# 7seg.net
KiCad netlist of a schematic drawn in EAGLE
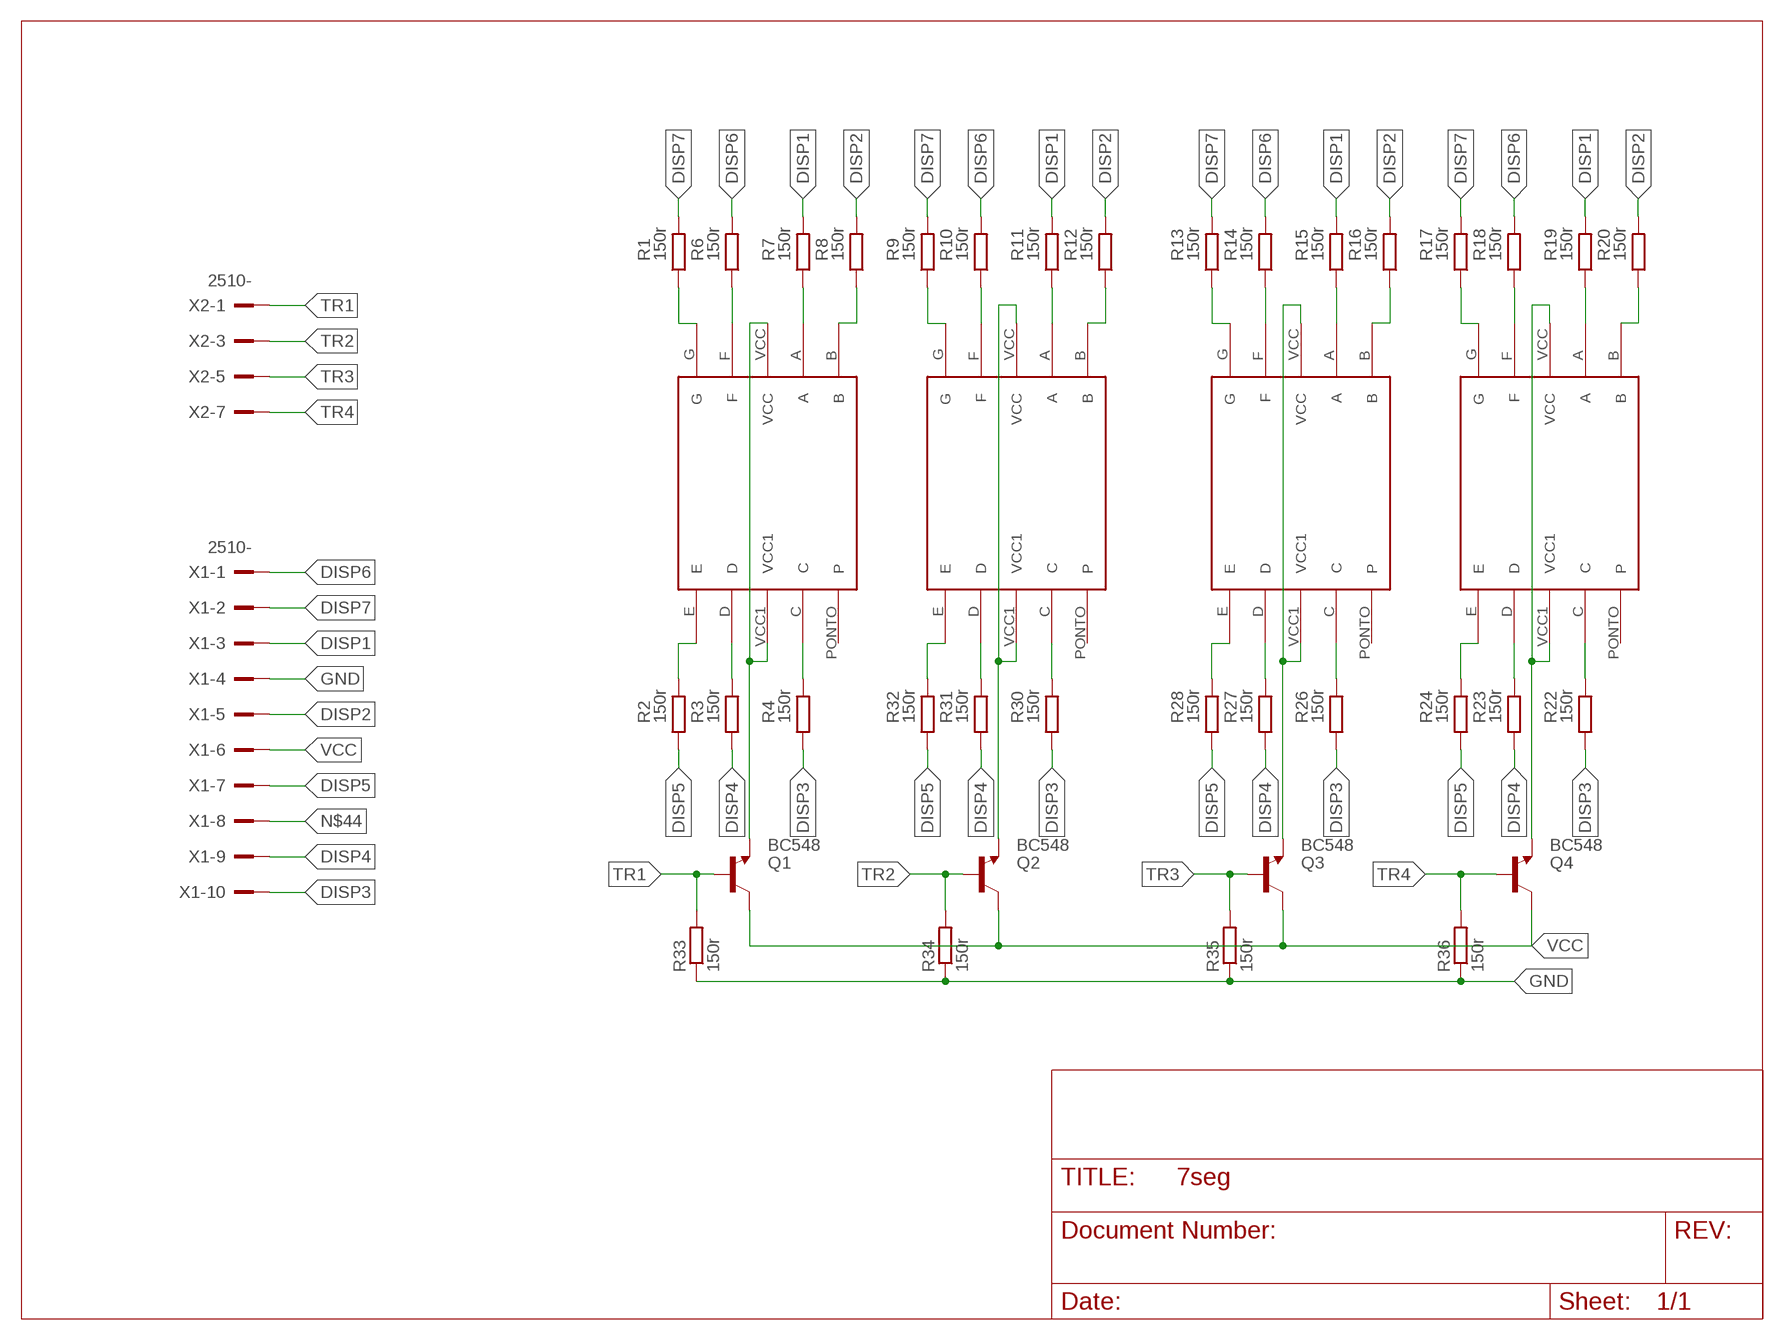
[diagram p0: schematic, sheet 1]

(export (version "E")
  (design (tool "Eeschema 10.0.6"))
  (components
    (comp (ref "Q1")
      (value "BC548")
      (footprint "eagle-import:TO92-EBC")
      (libsource (lib "eagle-import") (part "BC548"))
    )
    (comp (ref "Q2")
      (value "BC548")
      (footprint "eagle-import:TO92-EBC")
      (libsource (lib "eagle-import") (part "BC548"))
    )
    (comp (ref "Q3")
      (value "BC548")
      (footprint "eagle-import:TO92-EBC")
      (libsource (lib "eagle-import") (part "BC548"))
    )
    (comp (ref "Q4")
      (value "BC548")
      (footprint "eagle-import:TO92-EBC")
      (libsource (lib "eagle-import") (part "BC548"))
    )
    (comp (ref "R1")
      (value "150r")
      (footprint "eagle-import:0204_ELVYS")
      (libsource (lib "eagle-import") (part "R-EU_"))
    )
    (comp (ref "R2")
      (value "150r")
      (footprint "eagle-import:0204_ELVYS")
      (libsource (lib "eagle-import") (part "R-EU_"))
    )
    (comp (ref "R3")
      (value "150r")
      (footprint "eagle-import:0204_ELVYS")
      (libsource (lib "eagle-import") (part "R-EU_"))
    )
    (comp (ref "R4")
      (value "150r")
      (footprint "eagle-import:0204_ELVYS")
      (libsource (lib "eagle-import") (part "R-EU_"))
    )
    (comp (ref "R6")
      (value "150r")
      (footprint "eagle-import:0204_ELVYS")
      (libsource (lib "eagle-import") (part "R-EU_"))
    )
    (comp (ref "R7")
      (value "150r")
      (footprint "eagle-import:0204_ELVYS")
      (libsource (lib "eagle-import") (part "R-EU_"))
    )
    (comp (ref "R8")
      (value "150r")
      (footprint "eagle-import:0204_ELVYS")
      (libsource (lib "eagle-import") (part "R-EU_"))
    )
    (comp (ref "R9")
      (value "150r")
      (footprint "eagle-import:0204_ELVYS")
      (libsource (lib "eagle-import") (part "R-EU_"))
    )
    (comp (ref "R10")
      (value "150r")
      (footprint "eagle-import:0204_ELVYS")
      (libsource (lib "eagle-import") (part "R-EU_"))
    )
    (comp (ref "R11")
      (value "150r")
      (footprint "eagle-import:0204_ELVYS")
      (libsource (lib "eagle-import") (part "R-EU_"))
    )
    (comp (ref "R12")
      (value "150r")
      (footprint "eagle-import:0204_ELVYS")
      (libsource (lib "eagle-import") (part "R-EU_"))
    )
    (comp (ref "R13")
      (value "150r")
      (footprint "eagle-import:0204_ELVYS")
      (libsource (lib "eagle-import") (part "R-EU_"))
    )
    (comp (ref "R14")
      (value "150r")
      (footprint "eagle-import:0204_ELVYS")
      (libsource (lib "eagle-import") (part "R-EU_"))
    )
    (comp (ref "R15")
      (value "150r")
      (footprint "eagle-import:0204_ELVYS")
      (libsource (lib "eagle-import") (part "R-EU_"))
    )
    (comp (ref "R16")
      (value "150r")
      (footprint "eagle-import:0204_ELVYS")
      (libsource (lib "eagle-import") (part "R-EU_"))
    )
    (comp (ref "R17")
      (value "150r")
      (footprint "eagle-import:0204_ELVYS")
      (libsource (lib "eagle-import") (part "R-EU_"))
    )
    (comp (ref "R18")
      (value "150r")
      (footprint "eagle-import:0204_ELVYS")
      (libsource (lib "eagle-import") (part "R-EU_"))
    )
    (comp (ref "R19")
      (value "150r")
      (footprint "eagle-import:0204_ELVYS")
      (libsource (lib "eagle-import") (part "R-EU_"))
    )
    (comp (ref "R20")
      (value "150r")
      (footprint "eagle-import:0204_ELVYS")
      (libsource (lib "eagle-import") (part "R-EU_"))
    )
    (comp (ref "R22")
      (value "150r")
      (footprint "eagle-import:0204_ELVYS")
      (libsource (lib "eagle-import") (part "R-EU_"))
    )
    (comp (ref "R23")
      (value "150r")
      (footprint "eagle-import:0204_ELVYS")
      (libsource (lib "eagle-import") (part "R-EU_"))
    )
    (comp (ref "R24")
      (value "150r")
      (footprint "eagle-import:0204_ELVYS")
      (libsource (lib "eagle-import") (part "R-EU_"))
    )
    (comp (ref "R26")
      (value "150r")
      (footprint "eagle-import:0204_ELVYS")
      (libsource (lib "eagle-import") (part "R-EU_"))
    )
    (comp (ref "R27")
      (value "150r")
      (footprint "eagle-import:0204_ELVYS")
      (libsource (lib "eagle-import") (part "R-EU_"))
    )
    (comp (ref "R28")
      (value "150r")
      (footprint "eagle-import:0204_ELVYS")
      (libsource (lib "eagle-import") (part "R-EU_"))
    )
    (comp (ref "R30")
      (value "150r")
      (footprint "eagle-import:0204_ELVYS")
      (libsource (lib "eagle-import") (part "R-EU_"))
    )
    (comp (ref "R31")
      (value "150r")
      (footprint "eagle-import:0204_ELVYS")
      (libsource (lib "eagle-import") (part "R-EU_"))
    )
    (comp (ref "R32")
      (value "150r")
      (footprint "eagle-import:0204_ELVYS")
      (libsource (lib "eagle-import") (part "R-EU_"))
    )
    (comp (ref "R33")
      (value "150r")
      (footprint "eagle-import:0204_ELVYS")
      (libsource (lib "eagle-import") (part "R-EU_"))
    )
    (comp (ref "R34")
      (value "150r")
      (footprint "eagle-import:0204_ELVYS")
      (libsource (lib "eagle-import") (part "R-EU_"))
    )
    (comp (ref "R35")
      (value "150r")
      (footprint "eagle-import:0204_ELVYS")
      (libsource (lib "eagle-import") (part "R-EU_"))
    )
    (comp (ref "R36")
      (value "150r")
      (footprint "eagle-import:0204_ELVYS")
      (libsource (lib "eagle-import") (part "R-EU_"))
    )
    (comp (ref "U$1")
      (value "HS-12101BS")
      (footprint "eagle-import:HS-12101BS")
      (libsource (lib "eagle-import") (part "HS-12101BS"))
    )
    (comp (ref "U$2")
      (value "HS-12101BS")
      (footprint "eagle-import:HS-12101BS")
      (libsource (lib "eagle-import") (part "HS-12101BS"))
    )
    (comp (ref "U$3")
      (value "HS-12101BS")
      (footprint "eagle-import:HS-12101BS")
      (libsource (lib "eagle-import") (part "HS-12101BS"))
    )
    (comp (ref "U$4")
      (value "HS-12101BS")
      (footprint "eagle-import:HS-12101BS")
      (libsource (lib "eagle-import") (part "HS-12101BS"))
    )
    (comp (ref "X1")
      (value "2510-")
      (footprint "eagle-import:PAK100_2500-10")
      (fields (field (name "MF") "3M") (field (name "MPN") "2510-6002UB"))
      (libsource (lib "eagle-import") (part "2510-"))
    )
    (comp (ref "X2")
      (value "2510-")
      (footprint "eagle-import:PAK100_2500-10")
      (fields (field (name "MF") "3M") (field (name "MPN") "2510-6002UB"))
      (libsource (lib "eagle-import") (part "2510-"))
    )
  )
  (nets
    (net (code "1") (name "DISP1") (class "Default")
      (node (ref "R11") (pin "P$2") (pinfunction "2_P$2") (pintype "passive"))
      (node (ref "R15") (pin "P$2") (pinfunction "2_P$2") (pintype "passive"))
      (node (ref "R19") (pin "P$2") (pinfunction "2_P$2") (pintype "passive"))
      (node (ref "R7") (pin "P$2") (pinfunction "2_P$2") (pintype "passive"))
      (node (ref "X1") (pin "3") (pinfunction "KL_3") (pintype "passive"))
    )
    (net (code "2") (name "DISP2") (class "Default")
      (node (ref "R12") (pin "P$2") (pinfunction "2_P$2") (pintype "passive"))
      (node (ref "R16") (pin "P$2") (pinfunction "2_P$2") (pintype "passive"))
      (node (ref "R20") (pin "P$2") (pinfunction "2_P$2") (pintype "passive"))
      (node (ref "R8") (pin "P$2") (pinfunction "2_P$2") (pintype "passive"))
      (node (ref "X1") (pin "5") (pinfunction "KL_5") (pintype "passive"))
    )
    (net (code "3") (name "DISP3") (class "Default")
      (node (ref "R22") (pin "P$1") (pinfunction "1_P$1") (pintype "passive"))
      (node (ref "R26") (pin "P$1") (pinfunction "1_P$1") (pintype "passive"))
      (node (ref "R30") (pin "P$1") (pinfunction "1_P$1") (pintype "passive"))
      (node (ref "R4") (pin "P$1") (pinfunction "1_P$1") (pintype "passive"))
      (node (ref "X1") (pin "10") (pinfunction "KL_10") (pintype "passive"))
    )
    (net (code "4") (name "DISP4") (class "Default")
      (node (ref "R23") (pin "P$1") (pinfunction "1_P$1") (pintype "passive"))
      (node (ref "R27") (pin "P$1") (pinfunction "1_P$1") (pintype "passive"))
      (node (ref "R3") (pin "P$1") (pinfunction "1_P$1") (pintype "passive"))
      (node (ref "R31") (pin "P$1") (pinfunction "1_P$1") (pintype "passive"))
      (node (ref "X1") (pin "9") (pinfunction "KL_9") (pintype "passive"))
    )
    (net (code "5") (name "DISP5") (class "Default")
      (node (ref "R2") (pin "P$1") (pinfunction "1_P$1") (pintype "passive"))
      (node (ref "R24") (pin "P$1") (pinfunction "1_P$1") (pintype "passive"))
      (node (ref "R28") (pin "P$1") (pinfunction "1_P$1") (pintype "passive"))
      (node (ref "R32") (pin "P$1") (pinfunction "1_P$1") (pintype "passive"))
      (node (ref "X1") (pin "7") (pinfunction "KL_7") (pintype "passive"))
    )
    (net (code "6") (name "DISP6") (class "Default")
      (node (ref "R10") (pin "P$2") (pinfunction "2_P$2") (pintype "passive"))
      (node (ref "R14") (pin "P$2") (pinfunction "2_P$2") (pintype "passive"))
      (node (ref "R18") (pin "P$2") (pinfunction "2_P$2") (pintype "passive"))
      (node (ref "R6") (pin "P$2") (pinfunction "2_P$2") (pintype "passive"))
      (node (ref "X1") (pin "1") (pinfunction "KL_1") (pintype "passive"))
    )
    (net (code "7") (name "DISP7") (class "Default")
      (node (ref "R1") (pin "P$2") (pinfunction "2_P$2") (pintype "passive"))
      (node (ref "R13") (pin "P$2") (pinfunction "2_P$2") (pintype "passive"))
      (node (ref "R17") (pin "P$2") (pinfunction "2_P$2") (pintype "passive"))
      (node (ref "R9") (pin "P$2") (pinfunction "2_P$2") (pintype "passive"))
      (node (ref "X1") (pin "2") (pinfunction "KL_2") (pintype "passive"))
    )
    (net (code "8") (name "GND") (class "Default")
      (node (ref "R33") (pin "P$1") (pinfunction "1_P$1") (pintype "passive"))
      (node (ref "R34") (pin "P$1") (pinfunction "1_P$1") (pintype "passive"))
      (node (ref "R35") (pin "P$1") (pinfunction "1_P$1") (pintype "passive"))
      (node (ref "R36") (pin "P$1") (pinfunction "1_P$1") (pintype "passive"))
      (node (ref "X1") (pin "4") (pinfunction "KL_4") (pintype "passive"))
    )
    (net (code "9") (name "N$44") (class "Default")
      (node (ref "X1") (pin "8") (pinfunction "KL_8") (pintype "passive"))
    )
    (net (code "10") (name "Net-(Q1-PadE)") (class "Default")
      (node (ref "Q1") (pin "E") (pinfunction "E_E") (pintype "passive"))
      (node (ref "U$1") (pin "VCC") (pinfunction "VCC_VCC") (pintype "power_in"))
      (node (ref "U$1") (pin "VCC1") (pinfunction "VCC1_VCC1") (pintype "power_in"))
    )
    (net (code "11") (name "Net-(Q2-PadE)") (class "Default")
      (node (ref "Q2") (pin "E") (pinfunction "E_E") (pintype "passive"))
      (node (ref "U$2") (pin "VCC") (pinfunction "VCC_VCC") (pintype "power_in"))
      (node (ref "U$2") (pin "VCC1") (pinfunction "VCC1_VCC1") (pintype "power_in"))
    )
    (net (code "12") (name "Net-(Q3-PadE)") (class "Default")
      (node (ref "Q3") (pin "E") (pinfunction "E_E") (pintype "passive"))
      (node (ref "U$3") (pin "VCC") (pinfunction "VCC_VCC") (pintype "power_in"))
      (node (ref "U$3") (pin "VCC1") (pinfunction "VCC1_VCC1") (pintype "power_in"))
    )
    (net (code "13") (name "Net-(Q4-PadE)") (class "Default")
      (node (ref "Q4") (pin "E") (pinfunction "E_E") (pintype "passive"))
      (node (ref "U$4") (pin "VCC") (pinfunction "VCC_VCC") (pintype "power_in"))
      (node (ref "U$4") (pin "VCC1") (pinfunction "VCC1_VCC1") (pintype "power_in"))
    )
    (net (code "14") (name "Net-(R1-1)") (class "Default")
      (node (ref "R1") (pin "P$1") (pinfunction "1_P$1") (pintype "passive"))
      (node (ref "U$1") (pin "G") (pinfunction "G_G") (pintype "bidirectional"))
    )
    (net (code "15") (name "Net-(R2-2)") (class "Default")
      (node (ref "R2") (pin "P$2") (pinfunction "2_P$2") (pintype "passive"))
      (node (ref "U$1") (pin "E") (pinfunction "E_E") (pintype "bidirectional"))
    )
    (net (code "16") (name "Net-(R3-2)") (class "Default")
      (node (ref "R3") (pin "P$2") (pinfunction "2_P$2") (pintype "passive"))
      (node (ref "U$1") (pin "D") (pinfunction "D_D") (pintype "bidirectional"))
    )
    (net (code "17") (name "Net-(R4-2)") (class "Default")
      (node (ref "R4") (pin "P$2") (pinfunction "2_P$2") (pintype "passive"))
      (node (ref "U$1") (pin "C") (pinfunction "C_C") (pintype "bidirectional"))
    )
    (net (code "18") (name "Net-(R6-1)") (class "Default")
      (node (ref "R6") (pin "P$1") (pinfunction "1_P$1") (pintype "passive"))
      (node (ref "U$1") (pin "F") (pinfunction "F_F") (pintype "bidirectional"))
    )
    (net (code "19") (name "Net-(R7-1)") (class "Default")
      (node (ref "R7") (pin "P$1") (pinfunction "1_P$1") (pintype "passive"))
      (node (ref "U$1") (pin "A") (pinfunction "A_A") (pintype "bidirectional"))
    )
    (net (code "20") (name "Net-(R8-1)") (class "Default")
      (node (ref "R8") (pin "P$1") (pinfunction "1_P$1") (pintype "passive"))
      (node (ref "U$1") (pin "B") (pinfunction "B_B") (pintype "bidirectional"))
    )
    (net (code "21") (name "Net-(R9-1)") (class "Default")
      (node (ref "R9") (pin "P$1") (pinfunction "1_P$1") (pintype "passive"))
      (node (ref "U$2") (pin "G") (pinfunction "G_G") (pintype "bidirectional"))
    )
    (net (code "22") (name "Net-(R10-1)") (class "Default")
      (node (ref "R10") (pin "P$1") (pinfunction "1_P$1") (pintype "passive"))
      (node (ref "U$2") (pin "F") (pinfunction "F_F") (pintype "bidirectional"))
    )
    (net (code "23") (name "Net-(R11-1)") (class "Default")
      (node (ref "R11") (pin "P$1") (pinfunction "1_P$1") (pintype "passive"))
      (node (ref "U$2") (pin "A") (pinfunction "A_A") (pintype "bidirectional"))
    )
    (net (code "24") (name "Net-(R12-1)") (class "Default")
      (node (ref "R12") (pin "P$1") (pinfunction "1_P$1") (pintype "passive"))
      (node (ref "U$2") (pin "B") (pinfunction "B_B") (pintype "bidirectional"))
    )
    (net (code "25") (name "Net-(R13-1)") (class "Default")
      (node (ref "R13") (pin "P$1") (pinfunction "1_P$1") (pintype "passive"))
      (node (ref "U$3") (pin "G") (pinfunction "G_G") (pintype "bidirectional"))
    )
    (net (code "26") (name "Net-(R14-1)") (class "Default")
      (node (ref "R14") (pin "P$1") (pinfunction "1_P$1") (pintype "passive"))
      (node (ref "U$3") (pin "F") (pinfunction "F_F") (pintype "bidirectional"))
    )
    (net (code "27") (name "Net-(R15-1)") (class "Default")
      (node (ref "R15") (pin "P$1") (pinfunction "1_P$1") (pintype "passive"))
      (node (ref "U$3") (pin "A") (pinfunction "A_A") (pintype "bidirectional"))
    )
    (net (code "28") (name "Net-(R16-1)") (class "Default")
      (node (ref "R16") (pin "P$1") (pinfunction "1_P$1") (pintype "passive"))
      (node (ref "U$3") (pin "B") (pinfunction "B_B") (pintype "bidirectional"))
    )
    (net (code "29") (name "Net-(R17-1)") (class "Default")
      (node (ref "R17") (pin "P$1") (pinfunction "1_P$1") (pintype "passive"))
      (node (ref "U$4") (pin "G") (pinfunction "G_G") (pintype "bidirectional"))
    )
    (net (code "30") (name "Net-(R18-1)") (class "Default")
      (node (ref "R18") (pin "P$1") (pinfunction "1_P$1") (pintype "passive"))
      (node (ref "U$4") (pin "F") (pinfunction "F_F") (pintype "bidirectional"))
    )
    (net (code "31") (name "Net-(R19-1)") (class "Default")
      (node (ref "R19") (pin "P$1") (pinfunction "1_P$1") (pintype "passive"))
      (node (ref "U$4") (pin "A") (pinfunction "A_A") (pintype "bidirectional"))
    )
    (net (code "32") (name "Net-(R20-1)") (class "Default")
      (node (ref "R20") (pin "P$1") (pinfunction "1_P$1") (pintype "passive"))
      (node (ref "U$4") (pin "B") (pinfunction "B_B") (pintype "bidirectional"))
    )
    (net (code "33") (name "Net-(R22-2)") (class "Default")
      (node (ref "R22") (pin "P$2") (pinfunction "2_P$2") (pintype "passive"))
      (node (ref "U$4") (pin "C") (pinfunction "C_C") (pintype "bidirectional"))
    )
    (net (code "34") (name "Net-(R23-2)") (class "Default")
      (node (ref "R23") (pin "P$2") (pinfunction "2_P$2") (pintype "passive"))
      (node (ref "U$4") (pin "D") (pinfunction "D_D") (pintype "bidirectional"))
    )
    (net (code "35") (name "Net-(R24-2)") (class "Default")
      (node (ref "R24") (pin "P$2") (pinfunction "2_P$2") (pintype "passive"))
      (node (ref "U$4") (pin "E") (pinfunction "E_E") (pintype "bidirectional"))
    )
    (net (code "36") (name "Net-(R26-2)") (class "Default")
      (node (ref "R26") (pin "P$2") (pinfunction "2_P$2") (pintype "passive"))
      (node (ref "U$3") (pin "C") (pinfunction "C_C") (pintype "bidirectional"))
    )
    (net (code "37") (name "Net-(R27-2)") (class "Default")
      (node (ref "R27") (pin "P$2") (pinfunction "2_P$2") (pintype "passive"))
      (node (ref "U$3") (pin "D") (pinfunction "D_D") (pintype "bidirectional"))
    )
    (net (code "38") (name "Net-(R28-2)") (class "Default")
      (node (ref "R28") (pin "P$2") (pinfunction "2_P$2") (pintype "passive"))
      (node (ref "U$3") (pin "E") (pinfunction "E_E") (pintype "bidirectional"))
    )
    (net (code "39") (name "Net-(R30-2)") (class "Default")
      (node (ref "R30") (pin "P$2") (pinfunction "2_P$2") (pintype "passive"))
      (node (ref "U$2") (pin "C") (pinfunction "C_C") (pintype "bidirectional"))
    )
    (net (code "40") (name "Net-(R31-2)") (class "Default")
      (node (ref "R31") (pin "P$2") (pinfunction "2_P$2") (pintype "passive"))
      (node (ref "U$2") (pin "D") (pinfunction "D_D") (pintype "bidirectional"))
    )
    (net (code "41") (name "Net-(R32-2)") (class "Default")
      (node (ref "R32") (pin "P$2") (pinfunction "2_P$2") (pintype "passive"))
      (node (ref "U$2") (pin "E") (pinfunction "E_E") (pintype "bidirectional"))
    )
    (net (code "42") (name "TR1") (class "Default")
      (node (ref "Q1") (pin "B") (pinfunction "B_B") (pintype "passive"))
      (node (ref "R33") (pin "P$2") (pinfunction "2_P$2") (pintype "passive"))
      (node (ref "X2") (pin "1") (pinfunction "KL_1") (pintype "passive"))
    )
    (net (code "43") (name "TR2") (class "Default")
      (node (ref "Q2") (pin "B") (pinfunction "B_B") (pintype "passive"))
      (node (ref "R34") (pin "P$2") (pinfunction "2_P$2") (pintype "passive"))
      (node (ref "X2") (pin "3") (pinfunction "KL_3") (pintype "passive"))
    )
    (net (code "44") (name "TR3") (class "Default")
      (node (ref "Q3") (pin "B") (pinfunction "B_B") (pintype "passive"))
      (node (ref "R35") (pin "P$2") (pinfunction "2_P$2") (pintype "passive"))
      (node (ref "X2") (pin "5") (pinfunction "KL_5") (pintype "passive"))
    )
    (net (code "45") (name "TR4") (class "Default")
      (node (ref "Q4") (pin "B") (pinfunction "B_B") (pintype "passive"))
      (node (ref "R36") (pin "P$2") (pinfunction "2_P$2") (pintype "passive"))
      (node (ref "X2") (pin "7") (pinfunction "KL_7") (pintype "passive"))
    )
    (net (code "46") (name "VCC") (class "Default")
      (node (ref "Q1") (pin "C") (pinfunction "C_C") (pintype "passive"))
      (node (ref "Q2") (pin "C") (pinfunction "C_C") (pintype "passive"))
      (node (ref "Q3") (pin "C") (pinfunction "C_C") (pintype "passive"))
      (node (ref "Q4") (pin "C") (pinfunction "C_C") (pintype "passive"))
      (node (ref "X1") (pin "6") (pinfunction "KL_6") (pintype "passive"))
    )
    (net (code "47") (name "unconnected-(U$1-P-PadPONTO)") (class "Default")
      (node (ref "U$1") (pin "PONTO") (pinfunction "P_PONTO") (pintype "bidirectional"))
    )
    (net (code "48") (name "unconnected-(U$2-P-PadPONTO)") (class "Default")
      (node (ref "U$2") (pin "PONTO") (pinfunction "P_PONTO") (pintype "bidirectional"))
    )
    (net (code "49") (name "unconnected-(U$3-P-PadPONTO)") (class "Default")
      (node (ref "U$3") (pin "PONTO") (pinfunction "P_PONTO") (pintype "bidirectional"))
    )
    (net (code "50") (name "unconnected-(U$4-P-PadPONTO)") (class "Default")
      (node (ref "U$4") (pin "PONTO") (pinfunction "P_PONTO") (pintype "bidirectional"))
    )
  )
)
